# Kirt-th.net
KiCad netlist of a schematic drawn in EAGLE
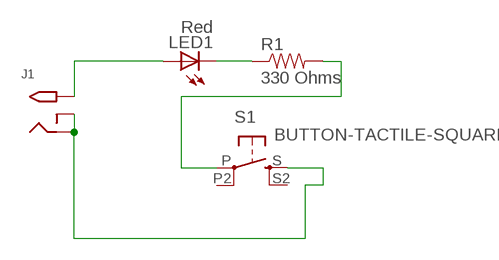
[diagram p0: schematic, sheet 1]

(export (version "E")
  (design (tool "Eeschema 10.0.6"))
  (components
    (comp (ref "J1")
      (value "2.1MMJACKTHM")
      (footprint "eagle-import:PJ-102A")
      (libsource (lib "eagle-import") (part "2.1MMJACKTHM"))
    )
    (comp (ref "LED1")
      (value "Red")
      (footprint "eagle-import:LED5MM")
      (libsource (lib "eagle-import") (part "LED5MM"))
    )
    (comp (ref "R1")
      (value "330 Ohms")
      (footprint "eagle-import:AXIAL-0.3")
      (libsource (lib "eagle-import") (part "RESISTORAXIAL-0.3"))
    )
    (comp (ref "S1")
      (value "BUTTON-TACTILE-SQUARE")
      (footprint "eagle-import:BUTTON-TACTILE-SQUARE-ADAFRUIT1010")
      (libsource (lib "eagle-import") (part "BUTTON-TACTILE-SQUARE"))
    )
  )
  (nets
    (net (code "1") (name "Net-(J1-PadRING)") (class "Default")
      (node (ref "J1") (pin "RING") (pinfunction "RING_RING") (pintype "bidirectional"))
      (node (ref "J1") (pin "RING_SW") (pinfunction "RING_SW_RING_SW") (pintype "bidirectional"))
      (node (ref "S1") (pin "S") (pinfunction "S_S") (pintype "passive"))
    )
    (net (code "2") (name "Net-(J1-PadTIP)") (class "Default")
      (node (ref "J1") (pin "TIP") (pinfunction "TIP_TIP") (pintype "bidirectional"))
      (node (ref "LED1") (pin "A") (pinfunction "A_A") (pintype "passive"))
    )
    (net (code "3") (name "Net-(LED1-C)") (class "Default")
      (node (ref "LED1") (pin "K") (pinfunction "C_K") (pintype "passive"))
      (node (ref "R1") (pin "P$1") (pinfunction "1_P$1") (pintype "passive"))
    )
    (net (code "4") (name "Net-(R1-2)") (class "Default")
      (node (ref "R1") (pin "P$2") (pinfunction "2_P$2") (pintype "passive"))
      (node (ref "S1") (pin "P") (pinfunction "P_P") (pintype "passive"))
    )
    (net (code "5") (name "unconnected-(S1-P1-PadP2)") (class "Default")
      (node (ref "S1") (pin "P2") (pinfunction "P1_P2") (pintype "passive"))
    )
    (net (code "6") (name "unconnected-(S1-S1-PadS2)") (class "Default")
      (node (ref "S1") (pin "S2") (pinfunction "S1_S2") (pintype "passive"))
    )
  )
)
